# STM32F103C4T6A.net
KiCad netlist of a schematic drawn in Altium Designer
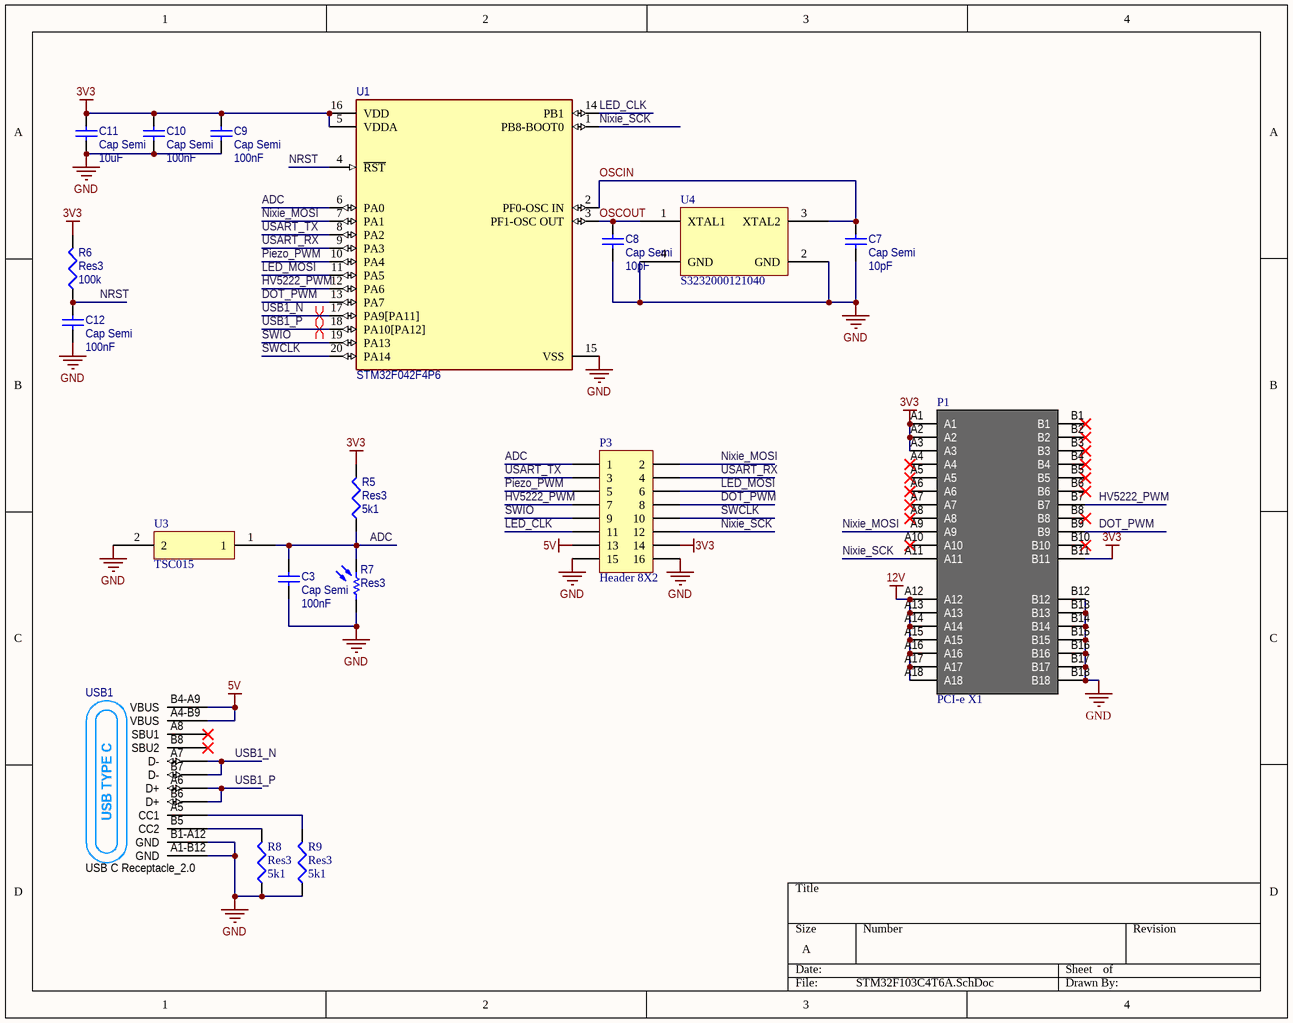
[diagram p0: STM32F103C4T6A.SchDoc]

(export (version "E")
  (design (tool "Eeschema 10.0.6"))
  (components
    (comp (ref "C3")
      (value "Cap Semi")
      (footprint "0402")
      (description "Capacitor (Semiconductor SIM Model)")
      (fields (field (name "ALTIUM_VALUE") "100nF") (field (name "PUBLISHER") "Altium Limited"))
      (libsource (lib "Miscellaneous Devices") (part "Cap Semi"))
    )
    (comp (ref "C7")
      (value "Cap Semi")
      (footprint "0402")
      (description "Capacitor (Semiconductor SIM Model)")
      (fields (field (name "ALTIUM_VALUE") "10pF") (field (name "PUBLISHER") "Altium Limited"))
      (libsource (lib "Miscellaneous Devices") (part "Cap Semi"))
    )
    (comp (ref "C8")
      (value "Cap Semi")
      (footprint "0402")
      (description "Capacitor (Semiconductor SIM Model)")
      (fields (field (name "ALTIUM_VALUE") "10pF") (field (name "PUBLISHER") "Altium Limited"))
      (libsource (lib "Miscellaneous Devices") (part "Cap Semi"))
    )
    (comp (ref "C9")
      (value "Cap Semi")
      (footprint "0402")
      (description "Capacitor (Semiconductor SIM Model)")
      (fields (field (name "ALTIUM_VALUE") "100nF") (field (name "PUBLISHER") "Altium Limited"))
      (libsource (lib "Miscellaneous Devices") (part "Cap Semi"))
    )
    (comp (ref "C10")
      (value "Cap Semi")
      (footprint "0402")
      (description "Capacitor (Semiconductor SIM Model)")
      (fields (field (name "ALTIUM_VALUE") "100nF") (field (name "PUBLISHER") "Altium Limited"))
      (libsource (lib "Miscellaneous Devices") (part "Cap Semi"))
    )
    (comp (ref "C11")
      (value "Cap Semi")
      (footprint "1608[0603]")
      (description "Capacitor (Semiconductor SIM Model)")
      (fields (field (name "ALTIUM_VALUE") "10uF") (field (name "PUBLISHER") "Altium Limited"))
      (libsource (lib "Miscellaneous Devices") (part "Cap Semi"))
    )
    (comp (ref "C12")
      (value "Cap Semi")
      (footprint "0402")
      (description "Capacitor (Semiconductor SIM Model)")
      (fields (field (name "ALTIUM_VALUE") "100nF") (field (name "PUBLISHER") "Altium Limited"))
      (libsource (lib "Miscellaneous Devices") (part "Cap Semi"))
    )
    (comp (ref "P1")
      (value "PCI-e X1")
      (footprint "10018784-10210TLF")
      (libsource (lib "kwa") (part "PCI-e X1"))
    )
    (comp (ref "P3")
      (value "Header 8X2")
      (footprint "HDR2X8")
      (description "Header, 8-Pin, Dual row")
      (fields (field (name "PUBLISHER") "Altium Limited"))
      (libsource (lib "Miscellaneous Connectors") (part "Header 8X2"))
    )
    (comp (ref "R5")
      (value "Res3")
      (footprint "J1-0603")
      (description "Resistor")
      (fields (field (name "ALTIUM_VALUE") "5k1") (field (name "PUBLISHER") "Altium Limited"))
      (libsource (lib "Miscellaneous Devices") (part "Res3"))
    )
    (comp (ref "R6")
      (value "Res3")
      (footprint "J1-0603")
      (description "Resistor")
      (fields (field (name "ALTIUM_VALUE") "100k") (field (name "PUBLISHER") "Altium Limited"))
      (libsource (lib "Miscellaneous Devices") (part "Res3"))
    )
    (comp (ref "R7")
      (value "Res3")
      (footprint "J1-0603")
      (description "Photoconductive Resistor, 200 kOhm, 100 V, 80 mW, -40 to 75 degC, 2-Pin THD, RoHS")
      (fields (field (name "MANUFACTURER") "Excelitas Technology"))
      (libsource (lib "Altium Content Vault") (part "PHOTO-RES-2"))
    )
    (comp (ref "R8")
      (value "Res3")
      (footprint "J1-0603")
      (description "Resistor")
      (fields (field (name "ALTIUM_VALUE") "5k1") (field (name "PUBLISHER") "Altium Limited"))
      (libsource (lib "Miscellaneous Devices") (part "Res3"))
    )
    (comp (ref "R9")
      (value "Res3")
      (footprint "J1-0603")
      (description "Resistor")
      (fields (field (name "ALTIUM_VALUE") "5k1") (field (name "PUBLISHER") "Altium Limited"))
      (libsource (lib "Miscellaneous Devices") (part "Res3"))
    )
    (comp (ref "U1")
      (value "STM32F042F4P6")
      (footprint "FP-TSSOP20-YA-MFG")
      (description "IC MCU 32BIT 16KB FLASH 20TSSOP")
      (fields
        (field (name "MANUFACTURER") "STMicroelectronics")
        (field (name "OCTOPART") "https://octopart.com/stm32f042f4p6-stmicroelectronics-34084829")
      )
      (libsource (lib "Altium Content Vault") (part "fb5839cf7c6cc5d149adc7a09845317"))
    )
    (comp (ref "U3")
      (value "TSC015")
      (footprint "TSC015")
      (description "Tactile Switch")
      (libsource (lib "Nixie_Clock") (part "TSC015"))
    )
    (comp (ref "U4")
      (value "S3232000121040")
      (footprint "SMD3225")
      (description "32MHz SMD Crystal Resonator")
      (libsource (lib "Nixie_Clock") (part "S3232000121040"))
    )
    (comp (ref "USB1")
      (value "USB C Receptacle_2.0")
      (footprint "TYPE-C16PIN-CONNECTOR")
      (libsource (lib "kwa") (part "USB C Receptacle_2.0"))
    )
  )
  (nets
    (net (code "1") (name "/ADC") (class "Default")
      (node (ref "C3") (pin "2") (pinfunction "2_2") (pintype "passive"))
      (node (ref "P3") (pin "1") (pinfunction "1_1") (pintype "passive"))
      (node (ref "R5") (pin "1") (pinfunction "1_1") (pintype "passive"))
      (node (ref "R7") (pin "2") (pinfunction "2_2") (pintype "passive"))
      (node (ref "U1") (pin "6") (pinfunction "PA0_6") (pintype "bidirectional"))
      (node (ref "U3") (pin "1") (pinfunction "1_1") (pintype "passive"))
    )
    (net (code "2") (name "/DOT_PWM") (class "Default")
      (node (ref "P1") (pin "B9") (pinfunction "B9_B9") (pintype "passive"))
      (node (ref "P3") (pin "8") (pinfunction "8_8") (pintype "passive"))
      (node (ref "U1") (pin "13") (pinfunction "PA7_13") (pintype "bidirectional"))
    )
    (net (code "3") (name "/HV5222_PWM") (class "Default")
      (node (ref "P1") (pin "B7") (pinfunction "B7_B7") (pintype "passive"))
      (node (ref "P3") (pin "7") (pinfunction "7_7") (pintype "passive"))
      (node (ref "U1") (pin "12") (pinfunction "PA6_12") (pintype "bidirectional"))
    )
    (net (code "4") (name "/LED_CLK") (class "Default")
      (node (ref "P3") (pin "11") (pinfunction "11_11") (pintype "passive"))
      (node (ref "U1") (pin "14") (pinfunction "PB1_14") (pintype "bidirectional"))
    )
    (net (code "5") (name "/LED_MOSI") (class "Default")
      (node (ref "P3") (pin "6") (pinfunction "6_6") (pintype "passive"))
      (node (ref "U1") (pin "11") (pinfunction "PA5_11") (pintype "bidirectional"))
    )
    (net (code "6") (name "/NRST") (class "Default")
      (node (ref "C12") (pin "2") (pinfunction "2_2") (pintype "passive"))
      (node (ref "R6") (pin "1") (pinfunction "1_1") (pintype "passive"))
      (node (ref "U1") (pin "4") (pinfunction "~{RST}_4") (pintype "input"))
    )
    (net (code "7") (name "/Nixie_MOSI") (class "Default")
      (node (ref "P1") (pin "A9") (pinfunction "A9_A9") (pintype "passive"))
      (node (ref "P3") (pin "2") (pinfunction "2_2") (pintype "passive"))
      (node (ref "U1") (pin "7") (pinfunction "PA1_7") (pintype "bidirectional"))
    )
    (net (code "8") (name "/Nixie_SCK") (class "Default")
      (node (ref "P1") (pin "A11") (pinfunction "A11_A11") (pintype "passive"))
      (node (ref "P3") (pin "12") (pinfunction "12_12") (pintype "passive"))
      (node (ref "U1") (pin "1") (pinfunction "PB8-BOOT0_1") (pintype "bidirectional"))
    )
    (net (code "9") (name "/OSCIN") (class "Default")
      (node (ref "C7") (pin "2") (pinfunction "2_2") (pintype "passive"))
      (node (ref "U1") (pin "2") (pinfunction "PF0-OSC_IN_2") (pintype "bidirectional"))
      (node (ref "U4") (pin "3") (pinfunction "XTAL2_3") (pintype "passive"))
    )
    (net (code "10") (name "/OSCOUT") (class "Default")
      (node (ref "C8") (pin "1") (pinfunction "1_1") (pintype "passive"))
      (node (ref "U1") (pin "3") (pinfunction "PF1-OSC_OUT_3") (pintype "bidirectional"))
      (node (ref "U4") (pin "1") (pinfunction "XTAL1_1") (pintype "passive"))
    )
    (net (code "11") (name "/Piezo_PWM") (class "Default")
      (node (ref "P3") (pin "5") (pinfunction "5_5") (pintype "passive"))
      (node (ref "U1") (pin "10") (pinfunction "PA4_10") (pintype "bidirectional"))
    )
    (net (code "12") (name "/SWCLK") (class "Default")
      (node (ref "P3") (pin "10") (pinfunction "10_10") (pintype "passive"))
      (node (ref "U1") (pin "20") (pinfunction "PA14_20") (pintype "bidirectional"))
    )
    (net (code "13") (name "/SWIO") (class "Default")
      (node (ref "P3") (pin "9") (pinfunction "9_9") (pintype "passive"))
      (node (ref "U1") (pin "19") (pinfunction "PA13_19") (pintype "bidirectional"))
    )
    (net (code "14") (name "/USART_RX") (class "Default")
      (node (ref "P3") (pin "4") (pinfunction "4_4") (pintype "passive"))
      (node (ref "U1") (pin "9") (pinfunction "PA3_9") (pintype "bidirectional"))
    )
    (net (code "15") (name "/USART_TX") (class "Default")
      (node (ref "P3") (pin "3") (pinfunction "3_3") (pintype "passive"))
      (node (ref "U1") (pin "8") (pinfunction "PA2_8") (pintype "bidirectional"))
    )
    (net (code "16") (name "/USB1_N") (class "Default")
      (node (ref "U1") (pin "17") (pinfunction "PA9[PA11]_17") (pintype "bidirectional"))
      (node (ref "USB1") (pin "A7") (pinfunction "D-_A7") (pintype "bidirectional"))
      (node (ref "USB1") (pin "B7") (pinfunction "D-_B7") (pintype "bidirectional"))
    )
    (net (code "17") (name "/USB1_P") (class "Default")
      (node (ref "U1") (pin "18") (pinfunction "PA10[PA12]_18") (pintype "bidirectional"))
      (node (ref "USB1") (pin "A6") (pinfunction "D+_A6") (pintype "bidirectional"))
      (node (ref "USB1") (pin "B6") (pinfunction "D+_B6") (pintype "bidirectional"))
    )
    (net (code "18") (name "3V3") (class "Default")
      (node (ref "C10") (pin "2") (pinfunction "2_2") (pintype "passive"))
      (node (ref "C11") (pin "2") (pinfunction "2_2") (pintype "passive"))
      (node (ref "C9") (pin "2") (pinfunction "2_2") (pintype "passive"))
      (node (ref "P1") (pin "A1") (pinfunction "A1_A1") (pintype "passive"))
      (node (ref "P1") (pin "A2") (pinfunction "A2_A2") (pintype "passive"))
      (node (ref "P1") (pin "A3") (pinfunction "A3_A3") (pintype "passive"))
      (node (ref "P1") (pin "B11") (pinfunction "B11_B11") (pintype "passive"))
      (node (ref "P3") (pin "14") (pinfunction "14_14") (pintype "passive"))
      (node (ref "R5") (pin "2") (pinfunction "2_2") (pintype "passive"))
      (node (ref "R6") (pin "2") (pinfunction "2_2") (pintype "passive"))
      (node (ref "U1") (pin "16") (pinfunction "VDD_16") (pintype "power_in"))
      (node (ref "U1") (pin "5") (pinfunction "VDDA_5") (pintype "power_in"))
    )
    (net (code "19") (name "5V") (class "Default")
      (node (ref "P3") (pin "13") (pinfunction "13_13") (pintype "passive"))
      (node (ref "USB1") (pin "A4-B9") (pinfunction "VBUS_A4-B9") (pintype "power_in"))
      (node (ref "USB1") (pin "B4-A9") (pinfunction "VBUS_B4-A9") (pintype "power_in"))
    )
    (net (code "20") (name "12V") (class "Default")
      (node (ref "P1") (pin "A12") (pinfunction "A12_A12") (pintype "passive"))
      (node (ref "P1") (pin "A13") (pinfunction "A13_A13") (pintype "passive"))
      (node (ref "P1") (pin "A14") (pinfunction "A14_A14") (pintype "passive"))
      (node (ref "P1") (pin "A15") (pinfunction "A15_A15") (pintype "passive"))
      (node (ref "P1") (pin "A16") (pinfunction "A16_A16") (pintype "passive"))
      (node (ref "P1") (pin "A17") (pinfunction "A17_A17") (pintype "passive"))
      (node (ref "P1") (pin "A18") (pinfunction "A18_A18") (pintype "passive"))
    )
    (net (code "21") (name "GND") (class "Default")
      (node (ref "C10") (pin "1") (pinfunction "1_1") (pintype "passive"))
      (node (ref "C11") (pin "1") (pinfunction "1_1") (pintype "passive"))
      (node (ref "C12") (pin "1") (pinfunction "1_1") (pintype "passive"))
      (node (ref "C3") (pin "1") (pinfunction "1_1") (pintype "passive"))
      (node (ref "C7") (pin "1") (pinfunction "1_1") (pintype "passive"))
      (node (ref "C8") (pin "2") (pinfunction "2_2") (pintype "passive"))
      (node (ref "C9") (pin "1") (pinfunction "1_1") (pintype "passive"))
      (node (ref "P1") (pin "B12") (pinfunction "B12_B12") (pintype "passive"))
      (node (ref "P1") (pin "B13") (pinfunction "B13_B13") (pintype "passive"))
      (node (ref "P1") (pin "B14") (pinfunction "B14_B14") (pintype "passive"))
      (node (ref "P1") (pin "B15") (pinfunction "B15_B15") (pintype "passive"))
      (node (ref "P1") (pin "B16") (pinfunction "B16_B16") (pintype "passive"))
      (node (ref "P1") (pin "B17") (pinfunction "B17_B17") (pintype "passive"))
      (node (ref "P1") (pin "B18") (pinfunction "B18_B18") (pintype "passive"))
      (node (ref "P3") (pin "15") (pinfunction "15_15") (pintype "passive"))
      (node (ref "P3") (pin "16") (pinfunction "16_16") (pintype "passive"))
      (node (ref "R7") (pin "1") (pinfunction "1_1") (pintype "passive"))
      (node (ref "R8") (pin "1") (pinfunction "1_1") (pintype "passive"))
      (node (ref "R9") (pin "1") (pinfunction "1_1") (pintype "passive"))
      (node (ref "U1") (pin "15") (pinfunction "VSS_15") (pintype "power_in"))
      (node (ref "U3") (pin "2") (pinfunction "2_2") (pintype "power_in"))
      (node (ref "U4") (pin "2") (pinfunction "GND_2") (pintype "power_in"))
      (node (ref "U4") (pin "4") (pinfunction "GND_4") (pintype "power_in"))
      (node (ref "USB1") (pin "A1-B12") (pinfunction "GND_A1-B12") (pintype "power_in"))
      (node (ref "USB1") (pin "B1-A12") (pinfunction "GND_B1-A12") (pintype "power_in"))
    )
    (net (code "22") (name "Net-(USB1-CC1)") (class "Default")
      (node (ref "R9") (pin "2") (pinfunction "2_2") (pintype "passive"))
      (node (ref "USB1") (pin "A5") (pinfunction "CC1_A5") (pintype "passive"))
    )
    (net (code "23") (name "Net-(USB1-CC2)") (class "Default")
      (node (ref "R8") (pin "2") (pinfunction "2_2") (pintype "passive"))
      (node (ref "USB1") (pin "B5") (pinfunction "CC2_B5") (pintype "passive"))
    )
    (net (code "24") (name "unconnected-(P1-PadA4)") (class "Default")
      (node (ref "P1") (pin "A4") (pinfunction "A4_A4") (pintype "passive+no_connect"))
    )
    (net (code "25") (name "unconnected-(P1-PadA5)") (class "Default")
      (node (ref "P1") (pin "A5") (pinfunction "A5_A5") (pintype "passive+no_connect"))
    )
    (net (code "26") (name "unconnected-(P1-PadA6)") (class "Default")
      (node (ref "P1") (pin "A6") (pinfunction "A6_A6") (pintype "passive+no_connect"))
    )
    (net (code "27") (name "unconnected-(P1-PadA7)") (class "Default")
      (node (ref "P1") (pin "A7") (pinfunction "A7_A7") (pintype "passive+no_connect"))
    )
    (net (code "28") (name "unconnected-(P1-PadA8)") (class "Default")
      (node (ref "P1") (pin "A8") (pinfunction "A8_A8") (pintype "passive+no_connect"))
    )
    (net (code "29") (name "unconnected-(P1-PadA10)") (class "Default")
      (node (ref "P1") (pin "A10") (pinfunction "A10_A10") (pintype "passive+no_connect"))
    )
    (net (code "30") (name "unconnected-(P1-PadB1)") (class "Default")
      (node (ref "P1") (pin "B1") (pinfunction "B1_B1") (pintype "passive+no_connect"))
    )
    (net (code "31") (name "unconnected-(P1-PadB2)") (class "Default")
      (node (ref "P1") (pin "B2") (pinfunction "B2_B2") (pintype "passive+no_connect"))
    )
    (net (code "32") (name "unconnected-(P1-PadB3)") (class "Default")
      (node (ref "P1") (pin "B3") (pinfunction "B3_B3") (pintype "passive+no_connect"))
    )
    (net (code "33") (name "unconnected-(P1-PadB4)") (class "Default")
      (node (ref "P1") (pin "B4") (pinfunction "B4_B4") (pintype "passive+no_connect"))
    )
    (net (code "34") (name "unconnected-(P1-PadB5)") (class "Default")
      (node (ref "P1") (pin "B5") (pinfunction "B5_B5") (pintype "passive+no_connect"))
    )
    (net (code "35") (name "unconnected-(P1-PadB6)") (class "Default")
      (node (ref "P1") (pin "B6") (pinfunction "B6_B6") (pintype "passive+no_connect"))
    )
    (net (code "36") (name "unconnected-(P1-PadB8)") (class "Default")
      (node (ref "P1") (pin "B8") (pinfunction "B8_B8") (pintype "passive+no_connect"))
    )
    (net (code "37") (name "unconnected-(P1-PadB10)") (class "Default")
      (node (ref "P1") (pin "B10") (pinfunction "B10_B10") (pintype "passive+no_connect"))
    )
    (net (code "38") (name "unconnected-(USB1-SBU1-PadA8)") (class "Default")
      (node (ref "USB1") (pin "A8") (pinfunction "SBU1_A8") (pintype "passive+no_connect"))
    )
    (net (code "39") (name "unconnected-(USB1-SBU2-PadB8)") (class "Default")
      (node (ref "USB1") (pin "B8") (pinfunction "SBU2_B8") (pintype "passive+no_connect"))
    )
  )
)
